# lab1_samarin_usb_rs485.net
KiCad netlist of a schematic drawn in Altium Designer
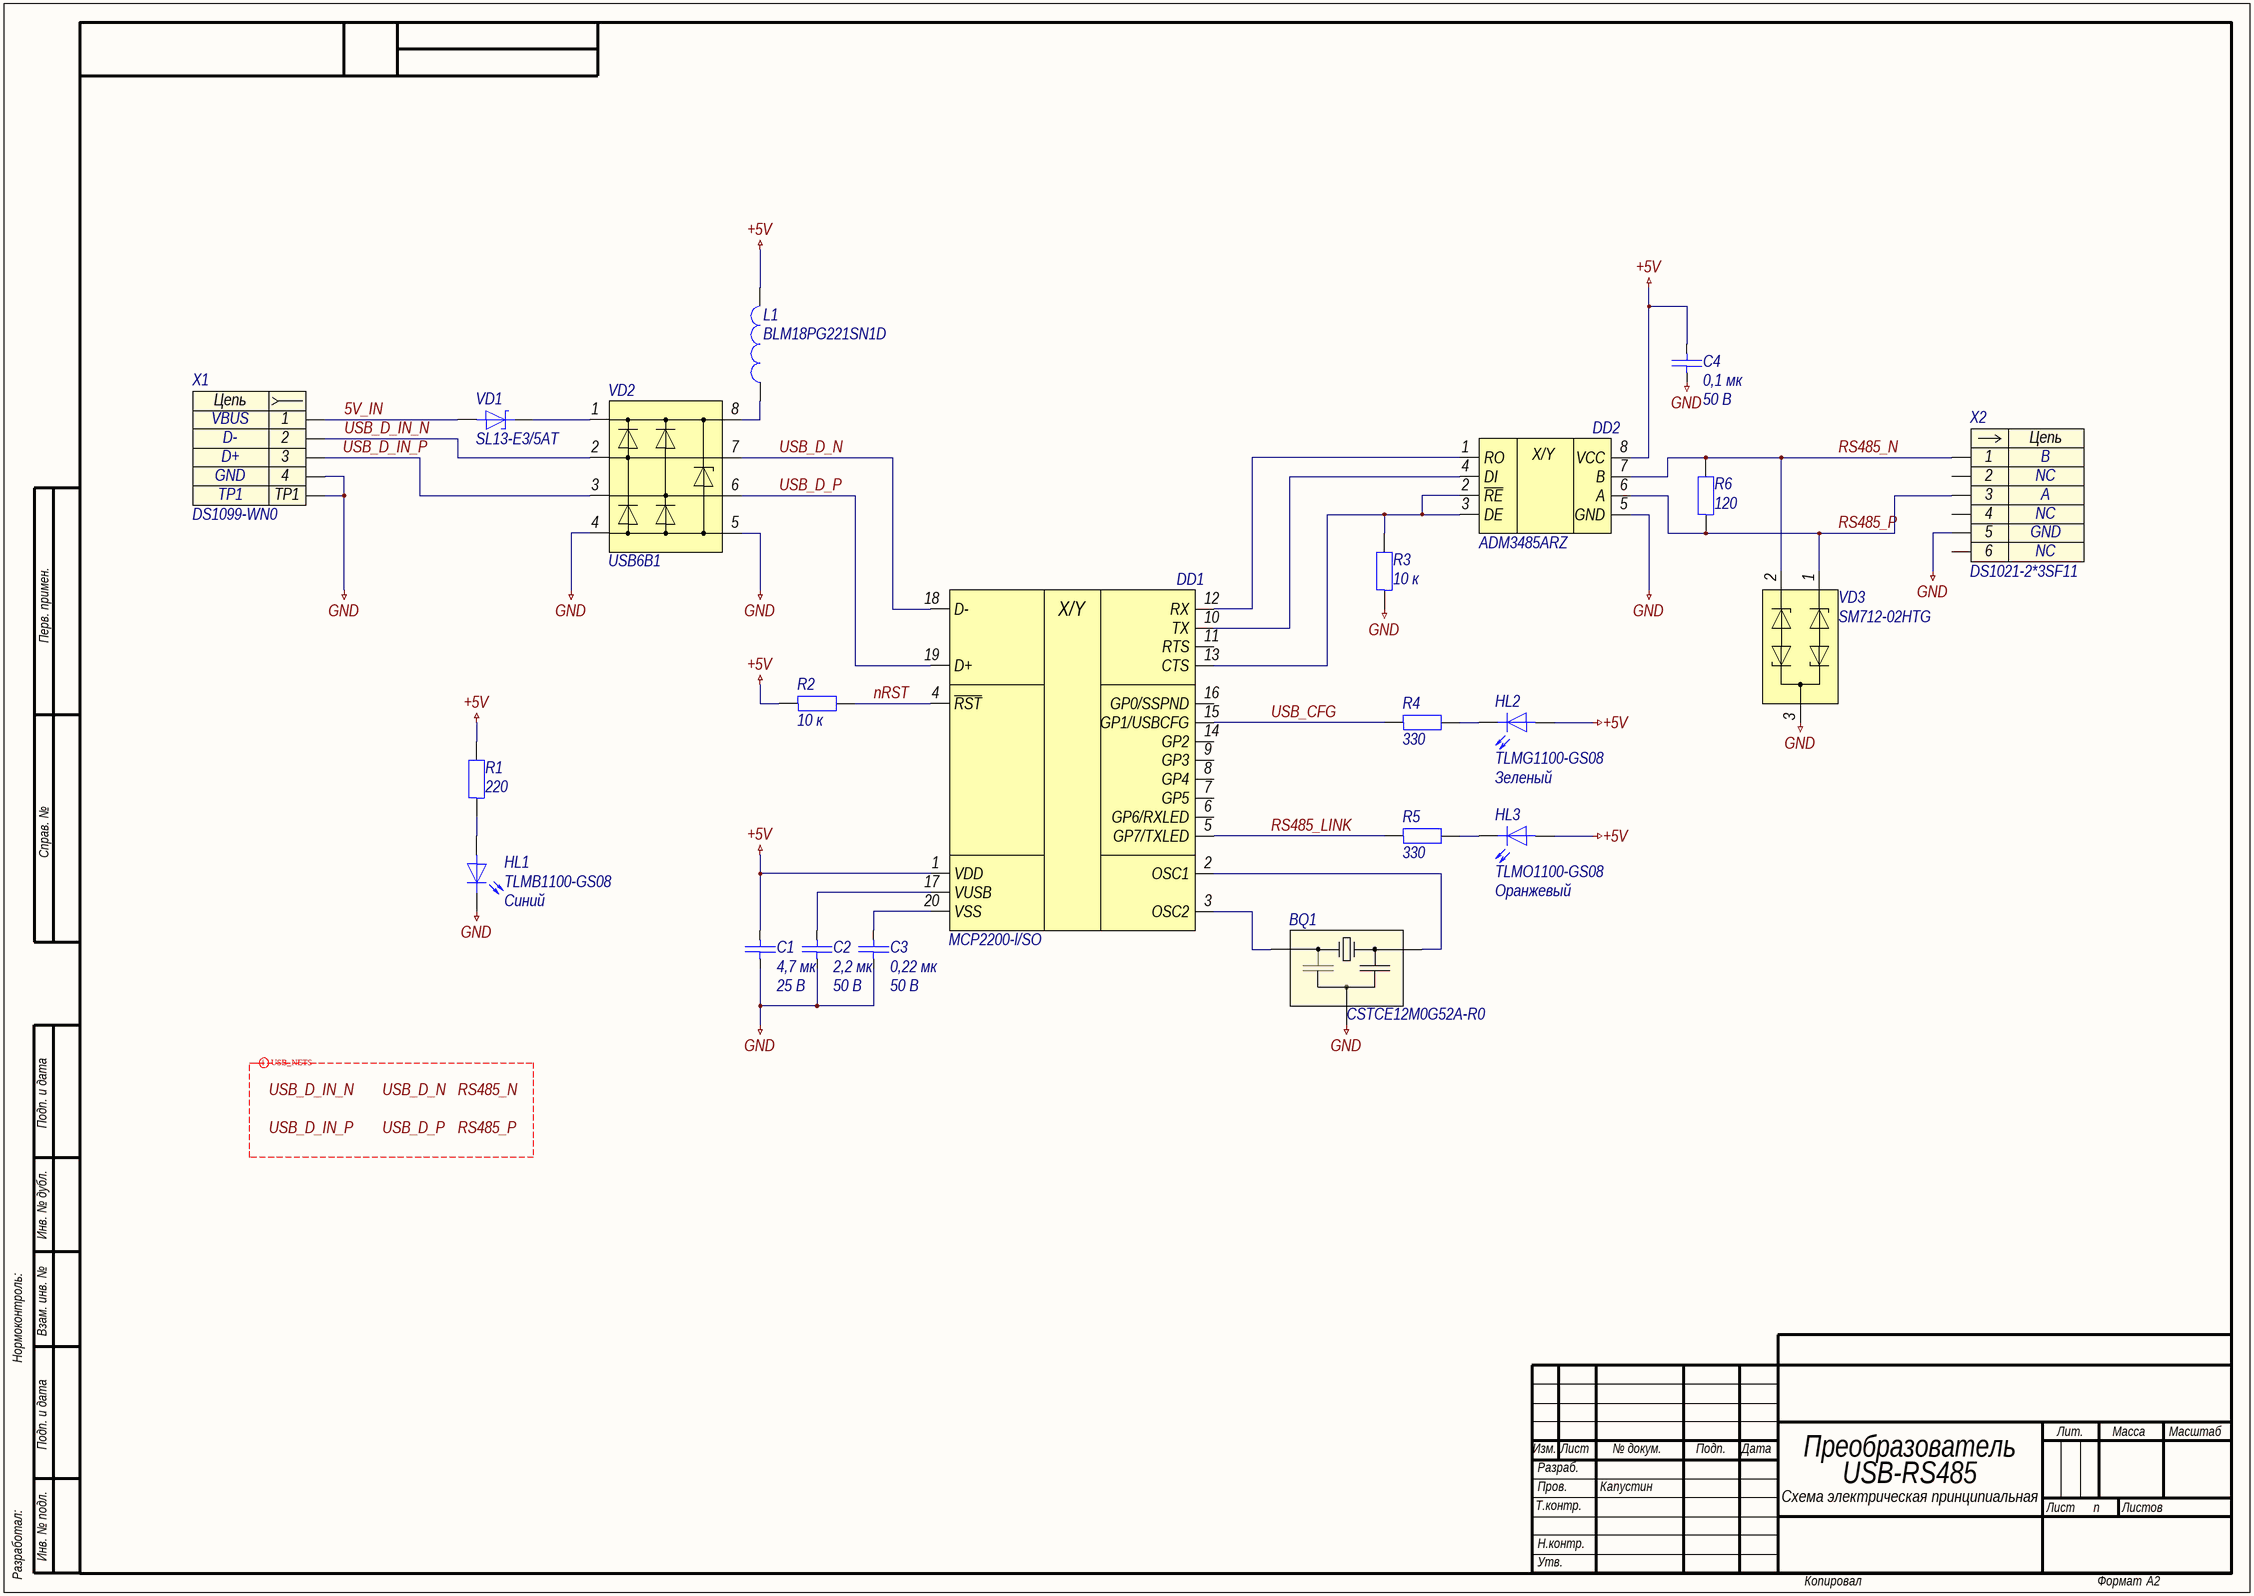
[diagram p0: lab1_samarin_usb_rs485.SchDoc]

(export (version "E")
  (design (tool "Eeschema 10.0.6"))
  (components
    (comp (ref "BQ1")
      (value "CSTCE12M0G52A-R0")
      (footprint "CSTCE-3-320X130X70")
      (description "=Описание")
      (libsource (lib "Database_Students") (part "CSTCE12M0G52A-R0"))
    )
    (comp (ref "C1")
      (value "4,7 мк")
      (footprint "C0603")
      (description "=Описание")
      (fields (field (name "НАПРЯЖЕНИЕ") "25 В"))
      (libsource (lib "Database_Students") (part "CAPACITOR-NONPOLAR"))
    )
    (comp (ref "C2")
      (value "2,2 мк")
      (footprint "C0603")
      (description "=Описание")
      (fields (field (name "НАПРЯЖЕНИЕ") "50 В"))
      (libsource (lib "Database_Students") (part "CAPACITOR-NONPOLAR"))
    )
    (comp (ref "C3")
      (value "0,22 мк")
      (footprint "C0603")
      (description "=Описание")
      (fields (field (name "НАПРЯЖЕНИЕ") "50 В"))
      (libsource (lib "Database_Students") (part "CAPACITOR-NONPOLAR"))
    )
    (comp (ref "C4")
      (value "0,1 мк")
      (footprint "C0603")
      (description "=Описание")
      (fields (field (name "НАПРЯЖЕНИЕ") "50 В"))
      (libsource (lib "Database_Students") (part "CAPACITOR-NONPOLAR"))
    )
    (comp (ref "DD1")
      (value "MCP2200-l/SO")
      (footprint "SOIC-20")
      (description "=Описание")
      (libsource (lib "Database_Students") (part "MCP2200-l/SO"))
    )
    (comp (ref "DD2")
      (value "ADM3485ARZ")
      (footprint "SOIC-8")
      (description "=Описание")
      (libsource (lib "Database_Students") (part "ADM3485ARZ"))
    )
    (comp (ref "HL1")
      (value "TLMB1100-GS08")
      (footprint "HL0603")
      (description "=Описание")
      (fields (field (name "COLOUR") "Синий"))
      (libsource (lib "Database_Students") (part "LED-COMMON"))
    )
    (comp (ref "HL2")
      (value "TLMG1100-GS08")
      (footprint "HL0603")
      (description "=Описание")
      (fields (field (name "COLOUR") "Зеленый"))
      (libsource (lib "Database_Students") (part "LED-COMMON"))
    )
    (comp (ref "HL3")
      (value "TLMO1100-GS08")
      (footprint "HL0603")
      (description "=Описание")
      (fields (field (name "COLOUR") "Оранжевый"))
      (libsource (lib "Database_Students") (part "LED-COMMON"))
    )
    (comp (ref "L1")
      (value "BLM18PG221SN1D")
      (footprint "BLM-2-0603")
      (description "=Описание")
      (libsource (lib "Database_Students") (part "FERRITE-BEAD"))
    )
    (comp (ref "R1")
      (value "220")
      (footprint "R0603")
      (description "=Описание")
      (libsource (lib "Database_Students") (part "R-COMMON"))
    )
    (comp (ref "R2")
      (value "10 к")
      (footprint "R0603")
      (description "=Описание")
      (libsource (lib "Database_Students") (part "R-COMMON"))
    )
    (comp (ref "R3")
      (value "10 к")
      (footprint "R0603")
      (description "=Описание")
      (libsource (lib "Database_Students") (part "R-COMMON"))
    )
    (comp (ref "R4")
      (value "330")
      (footprint "R0603")
      (description "=Описание")
      (libsource (lib "Database_Students") (part "R-COMMON"))
    )
    (comp (ref "R5")
      (value "330")
      (footprint "R0603")
      (description "=Описание")
      (libsource (lib "Database_Students") (part "R-COMMON"))
    )
    (comp (ref "R6")
      (value "120")
      (footprint "R0603")
      (description "=Описание")
      (libsource (lib "Database_Students") (part "R-COMMON"))
    )
    (comp (ref "VD1")
      (value "SL13-E3/5AT")
      (footprint "DO-214AC")
      (description "=Описание")
      (libsource (lib "Database_Students") (part "DIODE-SCHOTTKY"))
    )
    (comp (ref "VD2")
      (value "USB6B1")
      (footprint "SOIC-8")
      (description "=Описание")
      (libsource (lib "Database_Students") (part "USB6B1"))
    )
    (comp (ref "VD3")
      (value "SM712-02HTG")
      (footprint "SOT-23-3")
      (description "=Описание")
      (libsource (lib "Database_Students") (part "SM712-02HTG"))
    )
    (comp (ref "X1")
      (value "DS1099-WN0")
      (footprint "DS1099-WN0")
      (description "=Описание")
      (libsource (lib "Database_Students") (part "HEADER-4-TP1-SCT"))
    )
    (comp (ref "X2")
      (value "DS1021-2*3SF11")
      (footprint "DS1021-2X3SF11")
      (description "=Описание")
      (libsource (lib "Database_Students") (part "HEADER-6-PLG"))
    )
  )
  (nets
    (net (code "1") (name "+5V") (class "Default")
      (node (ref "C1") (pin "1") (pinfunction "1_1") (pintype "passive"))
      (node (ref "C4") (pin "1") (pinfunction "1_1") (pintype "passive"))
      (node (ref "DD1") (pin "1") (pinfunction "VDD_1") (pintype "passive"))
      (node (ref "DD2") (pin "8") (pinfunction "VCC_8") (pintype "passive"))
      (node (ref "HL2") (pin "2") (pinfunction "2_2") (pintype "passive"))
      (node (ref "HL3") (pin "2") (pinfunction "2_2") (pintype "passive"))
      (node (ref "L1") (pin "2") (pinfunction "2_2") (pintype "passive"))
      (node (ref "R1") (pin "2") (pinfunction "2_2") (pintype "passive"))
      (node (ref "R2") (pin "1") (pinfunction "1_1") (pintype "passive"))
    )
    (net (code "2") (name "/5V_IN") (class "Default")
      (node (ref "VD1") (pin "2") (pinfunction "2_2") (pintype "passive"))
      (node (ref "X1") (pin "1") (pinfunction "1_1") (pintype "passive"))
    )
    (net (code "3") (name "/RS485_LINK") (class "Default")
      (node (ref "DD1") (pin "5") (pinfunction "GP7/TXLED_5") (pintype "passive"))
      (node (ref "R5") (pin "1") (pinfunction "1_1") (pintype "passive"))
    )
    (net (code "4") (name "/RS485_N") (class "Default")
      (node (ref "DD2") (pin "7") (pinfunction "B_7") (pintype "passive"))
      (node (ref "R6") (pin "2") (pinfunction "2_2") (pintype "passive"))
      (node (ref "VD3") (pin "2") (pinfunction "2_2") (pintype "passive"))
      (node (ref "X2") (pin "1") (pinfunction "1_1") (pintype "passive"))
    )
    (net (code "5") (name "/RS485_P") (class "Default")
      (node (ref "DD2") (pin "6") (pinfunction "A_6") (pintype "passive"))
      (node (ref "R6") (pin "1") (pinfunction "1_1") (pintype "passive"))
      (node (ref "VD3") (pin "1") (pinfunction "1_1") (pintype "passive"))
      (node (ref "X2") (pin "3") (pinfunction "3_3") (pintype "passive"))
    )
    (net (code "6") (name "/USB_CFG") (class "Default")
      (node (ref "DD1") (pin "15") (pinfunction "GP1/USBCFG_15") (pintype "passive"))
      (node (ref "R4") (pin "1") (pinfunction "1_1") (pintype "passive"))
    )
    (net (code "7") (name "/USB_D_IN_N") (class "Default")
      (node (ref "VD2") (pin "2") (pinfunction "2_2") (pintype "passive"))
      (node (ref "X1") (pin "2") (pinfunction "2_2") (pintype "passive"))
    )
    (net (code "8") (name "/USB_D_IN_P") (class "Default")
      (node (ref "VD2") (pin "3") (pinfunction "3_3") (pintype "passive"))
      (node (ref "X1") (pin "3") (pinfunction "3_3") (pintype "passive"))
    )
    (net (code "9") (name "/USB_D_N") (class "Default")
      (node (ref "DD1") (pin "18") (pinfunction "D-_18") (pintype "passive"))
      (node (ref "VD2") (pin "7") (pinfunction "7_7") (pintype "passive"))
    )
    (net (code "10") (name "/USB_D_P") (class "Default")
      (node (ref "DD1") (pin "19") (pinfunction "D+_19") (pintype "passive"))
      (node (ref "VD2") (pin "6") (pinfunction "6_6") (pintype "passive"))
    )
    (net (code "11") (name "/nRST") (class "Default")
      (node (ref "DD1") (pin "4") (pinfunction "~{RST}_4") (pintype "passive"))
      (node (ref "R2") (pin "2") (pinfunction "2_2") (pintype "passive"))
    )
    (net (code "12") (name "GND") (class "Default")
      (node (ref "BQ1") (pin "2") (pinfunction "2_2") (pintype "passive"))
      (node (ref "C1") (pin "2") (pinfunction "2_2") (pintype "passive"))
      (node (ref "C2") (pin "2") (pinfunction "2_2") (pintype "passive"))
      (node (ref "C3") (pin "2") (pinfunction "2_2") (pintype "passive"))
      (node (ref "C4") (pin "2") (pinfunction "2_2") (pintype "passive"))
      (node (ref "DD2") (pin "5") (pinfunction "GND_5") (pintype "passive"))
      (node (ref "HL1") (pin "1") (pinfunction "1_1") (pintype "passive"))
      (node (ref "R3") (pin "1") (pinfunction "1_1") (pintype "passive"))
      (node (ref "VD2") (pin "4") (pinfunction "4_4") (pintype "passive"))
      (node (ref "VD2") (pin "5") (pinfunction "5_5") (pintype "passive"))
      (node (ref "VD3") (pin "3") (pinfunction "3_3") (pintype "passive"))
      (node (ref "X1") (pin "4") (pinfunction "4_4") (pintype "passive"))
      (node (ref "X1") (pin "TP1") (pinfunction "TP1_TP1") (pintype "passive"))
      (node (ref "X2") (pin "5") (pinfunction "5_5") (pintype "passive"))
    )
    (net (code "13") (name "Net-(DD1-CTS)") (class "Default")
      (node (ref "DD1") (pin "13") (pinfunction "CTS_13") (pintype "passive"))
      (node (ref "DD2") (pin "2") (pinfunction "~{RE}_2") (pintype "passive"))
      (node (ref "DD2") (pin "3") (pinfunction "DE_3") (pintype "passive"))
      (node (ref "R3") (pin "2") (pinfunction "2_2") (pintype "passive"))
    )
    (net (code "14") (name "Net-(DD1-OSC1)") (class "Default")
      (node (ref "BQ1") (pin "1") (pinfunction "1_1") (pintype "passive"))
      (node (ref "DD1") (pin "2") (pinfunction "OSC1_2") (pintype "passive"))
    )
    (net (code "15") (name "Net-(DD1-OSC2)") (class "Default")
      (node (ref "BQ1") (pin "3") (pinfunction "3_3") (pintype "passive"))
      (node (ref "DD1") (pin "3") (pinfunction "OSC2_3") (pintype "passive"))
    )
    (net (code "16") (name "Net-(DD1-RX)") (class "Default")
      (node (ref "DD1") (pin "12") (pinfunction "RX_12") (pintype "passive"))
      (node (ref "DD2") (pin "1") (pinfunction "RO_1") (pintype "passive"))
    )
    (net (code "17") (name "Net-(DD1-TX)") (class "Default")
      (node (ref "DD1") (pin "10") (pinfunction "TX_10") (pintype "passive"))
      (node (ref "DD2") (pin "4") (pinfunction "DI_4") (pintype "passive"))
    )
    (net (code "18") (name "Net-(DD1-VSS)") (class "Default")
      (node (ref "C3") (pin "1") (pinfunction "1_1") (pintype "passive"))
      (node (ref "DD1") (pin "20") (pinfunction "VSS_20") (pintype "passive"))
    )
    (net (code "19") (name "Net-(DD1-VUSB)") (class "Default")
      (node (ref "C2") (pin "1") (pinfunction "1_1") (pintype "passive"))
      (node (ref "DD1") (pin "17") (pinfunction "VUSB_17") (pintype "passive"))
    )
    (net (code "20") (name "Net-(HL1-Pad2)") (class "Default")
      (node (ref "HL1") (pin "2") (pinfunction "2_2") (pintype "passive"))
      (node (ref "R1") (pin "1") (pinfunction "1_1") (pintype "passive"))
    )
    (net (code "21") (name "Net-(HL2-Pad1)") (class "Default")
      (node (ref "HL2") (pin "1") (pinfunction "1_1") (pintype "passive"))
      (node (ref "R4") (pin "2") (pinfunction "2_2") (pintype "passive"))
    )
    (net (code "22") (name "Net-(HL3-Pad1)") (class "Default")
      (node (ref "HL3") (pin "1") (pinfunction "1_1") (pintype "passive"))
      (node (ref "R5") (pin "2") (pinfunction "2_2") (pintype "passive"))
    )
    (net (code "23") (name "Net-(L1-Pad1)") (class "Default")
      (node (ref "L1") (pin "1") (pinfunction "1_1") (pintype "passive"))
      (node (ref "VD2") (pin "8") (pinfunction "8_8") (pintype "passive"))
    )
    (net (code "24") (name "Net-(VD1-Pad1)") (class "Default")
      (node (ref "VD1") (pin "1") (pinfunction "1_1") (pintype "passive"))
      (node (ref "VD2") (pin "1") (pinfunction "1_1") (pintype "passive"))
    )
    (net (code "25") (name "unconnected-(DD1-GP0{slash}SSPND-Pad16)") (class "Default")
      (node (ref "DD1") (pin "16") (pinfunction "GP0/SSPND_16") (pintype "passive"))
    )
    (net (code "26") (name "unconnected-(DD1-GP2-Pad14)") (class "Default")
      (node (ref "DD1") (pin "14") (pinfunction "GP2_14") (pintype "passive"))
    )
    (net (code "27") (name "unconnected-(DD1-GP3-Pad9)") (class "Default")
      (node (ref "DD1") (pin "9") (pinfunction "GP3_9") (pintype "passive"))
    )
    (net (code "28") (name "unconnected-(DD1-GP4-Pad8)") (class "Default")
      (node (ref "DD1") (pin "8") (pinfunction "GP4_8") (pintype "passive"))
    )
    (net (code "29") (name "unconnected-(DD1-GP5-Pad7)") (class "Default")
      (node (ref "DD1") (pin "7") (pinfunction "GP5_7") (pintype "passive"))
    )
    (net (code "30") (name "unconnected-(DD1-GP6{slash}RXLED-Pad6)") (class "Default")
      (node (ref "DD1") (pin "6") (pinfunction "GP6/RXLED_6") (pintype "passive"))
    )
    (net (code "31") (name "unconnected-(DD1-RTS-Pad11)") (class "Default")
      (node (ref "DD1") (pin "11") (pinfunction "RTS_11") (pintype "passive"))
    )
    (net (code "32") (name "unconnected-(X2-Pad2)") (class "Default")
      (node (ref "X2") (pin "2") (pinfunction "2_2") (pintype "passive"))
    )
    (net (code "33") (name "unconnected-(X2-Pad4)") (class "Default")
      (node (ref "X2") (pin "4") (pinfunction "4_4") (pintype "passive"))
    )
    (net (code "34") (name "unconnected-(X2-Pad6)") (class "Default")
      (node (ref "X2") (pin "6") (pinfunction "6_6") (pintype "passive"))
    )
  )
)
